# Lipo_Charger.net
KiCad netlist of a schematic drawn in Altium Designer
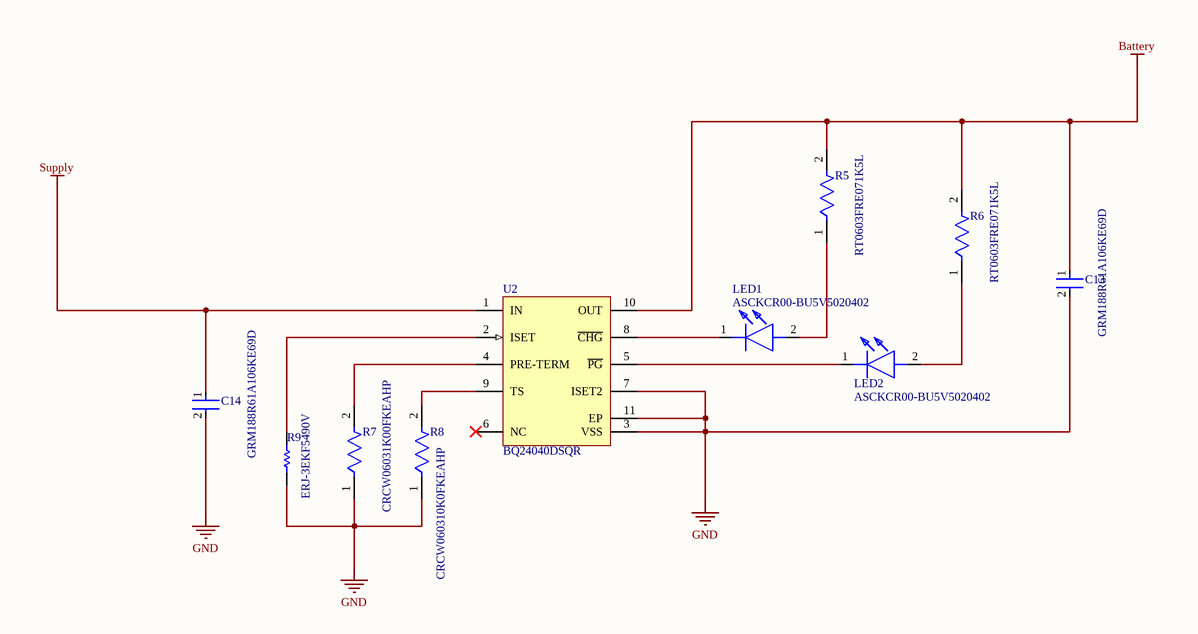
[diagram p0: Lipo_Charger.SchDoc]

(export (version "E")
  (design (tool "Eeschema 10.0.6"))
  (components
    (comp (ref "C13")
      (value "GRM188R61A106KE69D")
      (footprint "FP-GRM18-0_15-MFG")
      (description "CAP CER 10UF 10V X5R 0603")
      (fields
        (field (name "OCTOPART") "https://octopart.com/grm188r61a106ke69d-murata-22851381")
        (field (name "MANUFACTURER") "Murata")
      )
      (libsource (lib "Altium Content Vault") (part "11868f565c42a9108669ba33697ecf6"))
    )
    (comp (ref "C14")
      (value "GRM188R61A106KE69D")
      (footprint "FP-GRM18-0_15-MFG")
      (description "CAP CER 10UF 10V X5R 0603")
      (fields
        (field (name "OCTOPART") "https://octopart.com/grm188r61a106ke69d-murata-22851381")
        (field (name "MANUFACTURER") "Murata")
      )
      (libsource (lib "Altium Content Vault") (part "11868f565c42a9108669ba33697ecf6"))
    )
    (comp (ref "LED1")
      (value "ASCKCR00-BU5V5020402")
      (footprint "SamacSys:ASCKCR00BU5V5020402")
      (description "LED")
      (fields (field (name "MOUSER PART NUMBER") "630-ASCKCR00BU5V5020"))
      (libsource (lib "*") (part "ASCKCR00-BU5V5020402"))
    )
    (comp (ref "LED2")
      (value "ASCKCR00-BU5V5020402")
      (footprint "SamacSys:ASCKCR00BU5V5020402")
      (description "LED")
      (fields (field (name "MOUSER PART NUMBER") "630-ASCKCR00BU5V5020"))
      (libsource (lib "*") (part "ASCKCR00-BU5V5020402"))
    )
    (comp (ref "R5")
      (value "RT0603FRE071K5L")
      (footprint "FP-RT0603-MFG")
      (description "RES SMD 1.5K OHM 1% 1/10W 0603")
      (fields
        (field (name "MANUFACTURER") "Yageo")
        (field (name "OCTOPART") "https://octopart.com/rt0603fre071k5l-yageo-39862564")
      )
      (libsource (lib "Altium Content Vault") (part "1029c3af85768c4190bb7ad29bc67b5"))
    )
    (comp (ref "R6")
      (value "RT0603FRE071K5L")
      (footprint "FP-RT0603-MFG")
      (description "RES SMD 1.5K OHM 1% 1/10W 0603")
      (fields
        (field (name "MANUFACTURER") "Yageo")
        (field (name "OCTOPART") "https://octopart.com/rt0603fre071k5l-yageo-39862564")
      )
      (libsource (lib "Altium Content Vault") (part "1029c3af85768c4190bb7ad29bc67b5"))
    )
    (comp (ref "R7")
      (value "CRCW06031K00FKEAHP")
      (footprint "FP-CRCW0603-HPe3-MFG")
      (description "RES Thick Film, 1kΩ, 1%, 0.33W, 100ppm/°C, 0603")
      (fields (field (name "TOLERANCE") "1%"))
      (libsource (lib "Altium Content Vault") (part "1029c3af85768c4190bb7ad29bc67b5"))
    )
    (comp (ref "R8")
      (value "CRCW060310K0FKEAHP")
      (footprint "FP-CRCW0603-HPe3-MFG")
      (description "RES SMD 10K OHM 1% 1/3W 0603")
      (fields (field (name "TOLERANCE") "1%"))
      (libsource (lib "Altium Content Vault") (part "1029c3af85768c4190bb7ad29bc67b5"))
    )
    (comp (ref "R9")
      (value "ERJ-3EKF5490V")
      (footprint "RESC1608X55X30ML15T15")
      (fields (field (name "MANUFACTURER") "Panasonic"))
      (libsource (lib "Altium Content Vault") (part "RES"))
    )
    (comp (ref "U2")
      (value "BQ24040DSQR")
      (footprint "DSQ0010A_V")
      (fields (field (name "MANUFACTURER") "Texas Instruments"))
      (libsource (lib "Altium Content Vault") (part "TI-BQ24040DSQ10-1500X900TP"))
    )
  )
  (nets
    (net (code "1") (name "Battery") (class "Default")
      (node (ref "C13") (pin "1") (pinfunction "1_1") (pintype "passive"))
      (node (ref "R5") (pin "2") (pinfunction "2_2") (pintype "passive"))
      (node (ref "R6") (pin "2") (pinfunction "2_2") (pintype "passive"))
      (node (ref "U2") (pin "10") (pinfunction "OUT_10") (pintype "power_in"))
    )
    (net (code "2") (name "GND") (class "Default")
      (node (ref "C13") (pin "2") (pinfunction "2_2") (pintype "passive"))
      (node (ref "C14") (pin "2") (pinfunction "2_2") (pintype "passive"))
      (node (ref "R7") (pin "1") (pinfunction "1_1") (pintype "passive"))
      (node (ref "R8") (pin "1") (pinfunction "1_1") (pintype "passive"))
      (node (ref "R9") (pin "1") (pinfunction "1_1") (pintype "passive"))
      (node (ref "U2") (pin "11") (pinfunction "EP_11") (pintype "power_in"))
      (node (ref "U2") (pin "3") (pinfunction "VSS_3") (pintype "power_in"))
      (node (ref "U2") (pin "7") (pinfunction "ISET2_7") (pintype "passive"))
    )
    (net (code "3") (name "Net-(LED1-A)") (class "Default")
      (node (ref "LED1") (pin "2") (pinfunction "A_2") (pintype "passive"))
      (node (ref "R5") (pin "1") (pinfunction "1_1") (pintype "passive"))
    )
    (net (code "4") (name "Net-(LED1-K)") (class "Default")
      (node (ref "LED1") (pin "1") (pinfunction "K_1") (pintype "passive"))
      (node (ref "U2") (pin "8") (pinfunction "~{CHG}_8") (pintype "tri_state"))
    )
    (net (code "5") (name "Net-(LED2-A)") (class "Default")
      (node (ref "LED2") (pin "2") (pinfunction "A_2") (pintype "passive"))
      (node (ref "R6") (pin "1") (pinfunction "1_1") (pintype "passive"))
    )
    (net (code "6") (name "Net-(LED2-K)") (class "Default")
      (node (ref "LED2") (pin "1") (pinfunction "K_1") (pintype "passive"))
      (node (ref "U2") (pin "5") (pinfunction "~{PG}_5") (pintype "tri_state"))
    )
    (net (code "7") (name "Net-(U2-ISET)") (class "Default")
      (node (ref "R9") (pin "2") (pinfunction "2_2") (pintype "passive"))
      (node (ref "U2") (pin "2") (pinfunction "ISET_2") (pintype "input"))
    )
    (net (code "8") (name "Net-(U2-PRE-TERM)") (class "Default")
      (node (ref "R7") (pin "2") (pinfunction "2_2") (pintype "passive"))
      (node (ref "U2") (pin "4") (pinfunction "PRE-TERM_4") (pintype "passive"))
    )
    (net (code "9") (name "Net-(U2-TS)") (class "Default")
      (node (ref "R8") (pin "2") (pinfunction "2_2") (pintype "passive"))
      (node (ref "U2") (pin "9") (pinfunction "TS_9") (pintype "passive"))
    )
    (net (code "10") (name "Supply") (class "Default")
      (node (ref "C14") (pin "1") (pinfunction "1_1") (pintype "passive"))
      (node (ref "U2") (pin "1") (pinfunction "IN_1") (pintype "power_in"))
    )
    (net (code "11") (name "unconnected-(U2-NC-Pad6)") (class "Default")
      (node (ref "U2") (pin "6") (pinfunction "NC_6") (pintype "passive+no_connect"))
    )
  )
)
